# top_level.net
KiCad netlist of a schematic drawn in Altium Designer
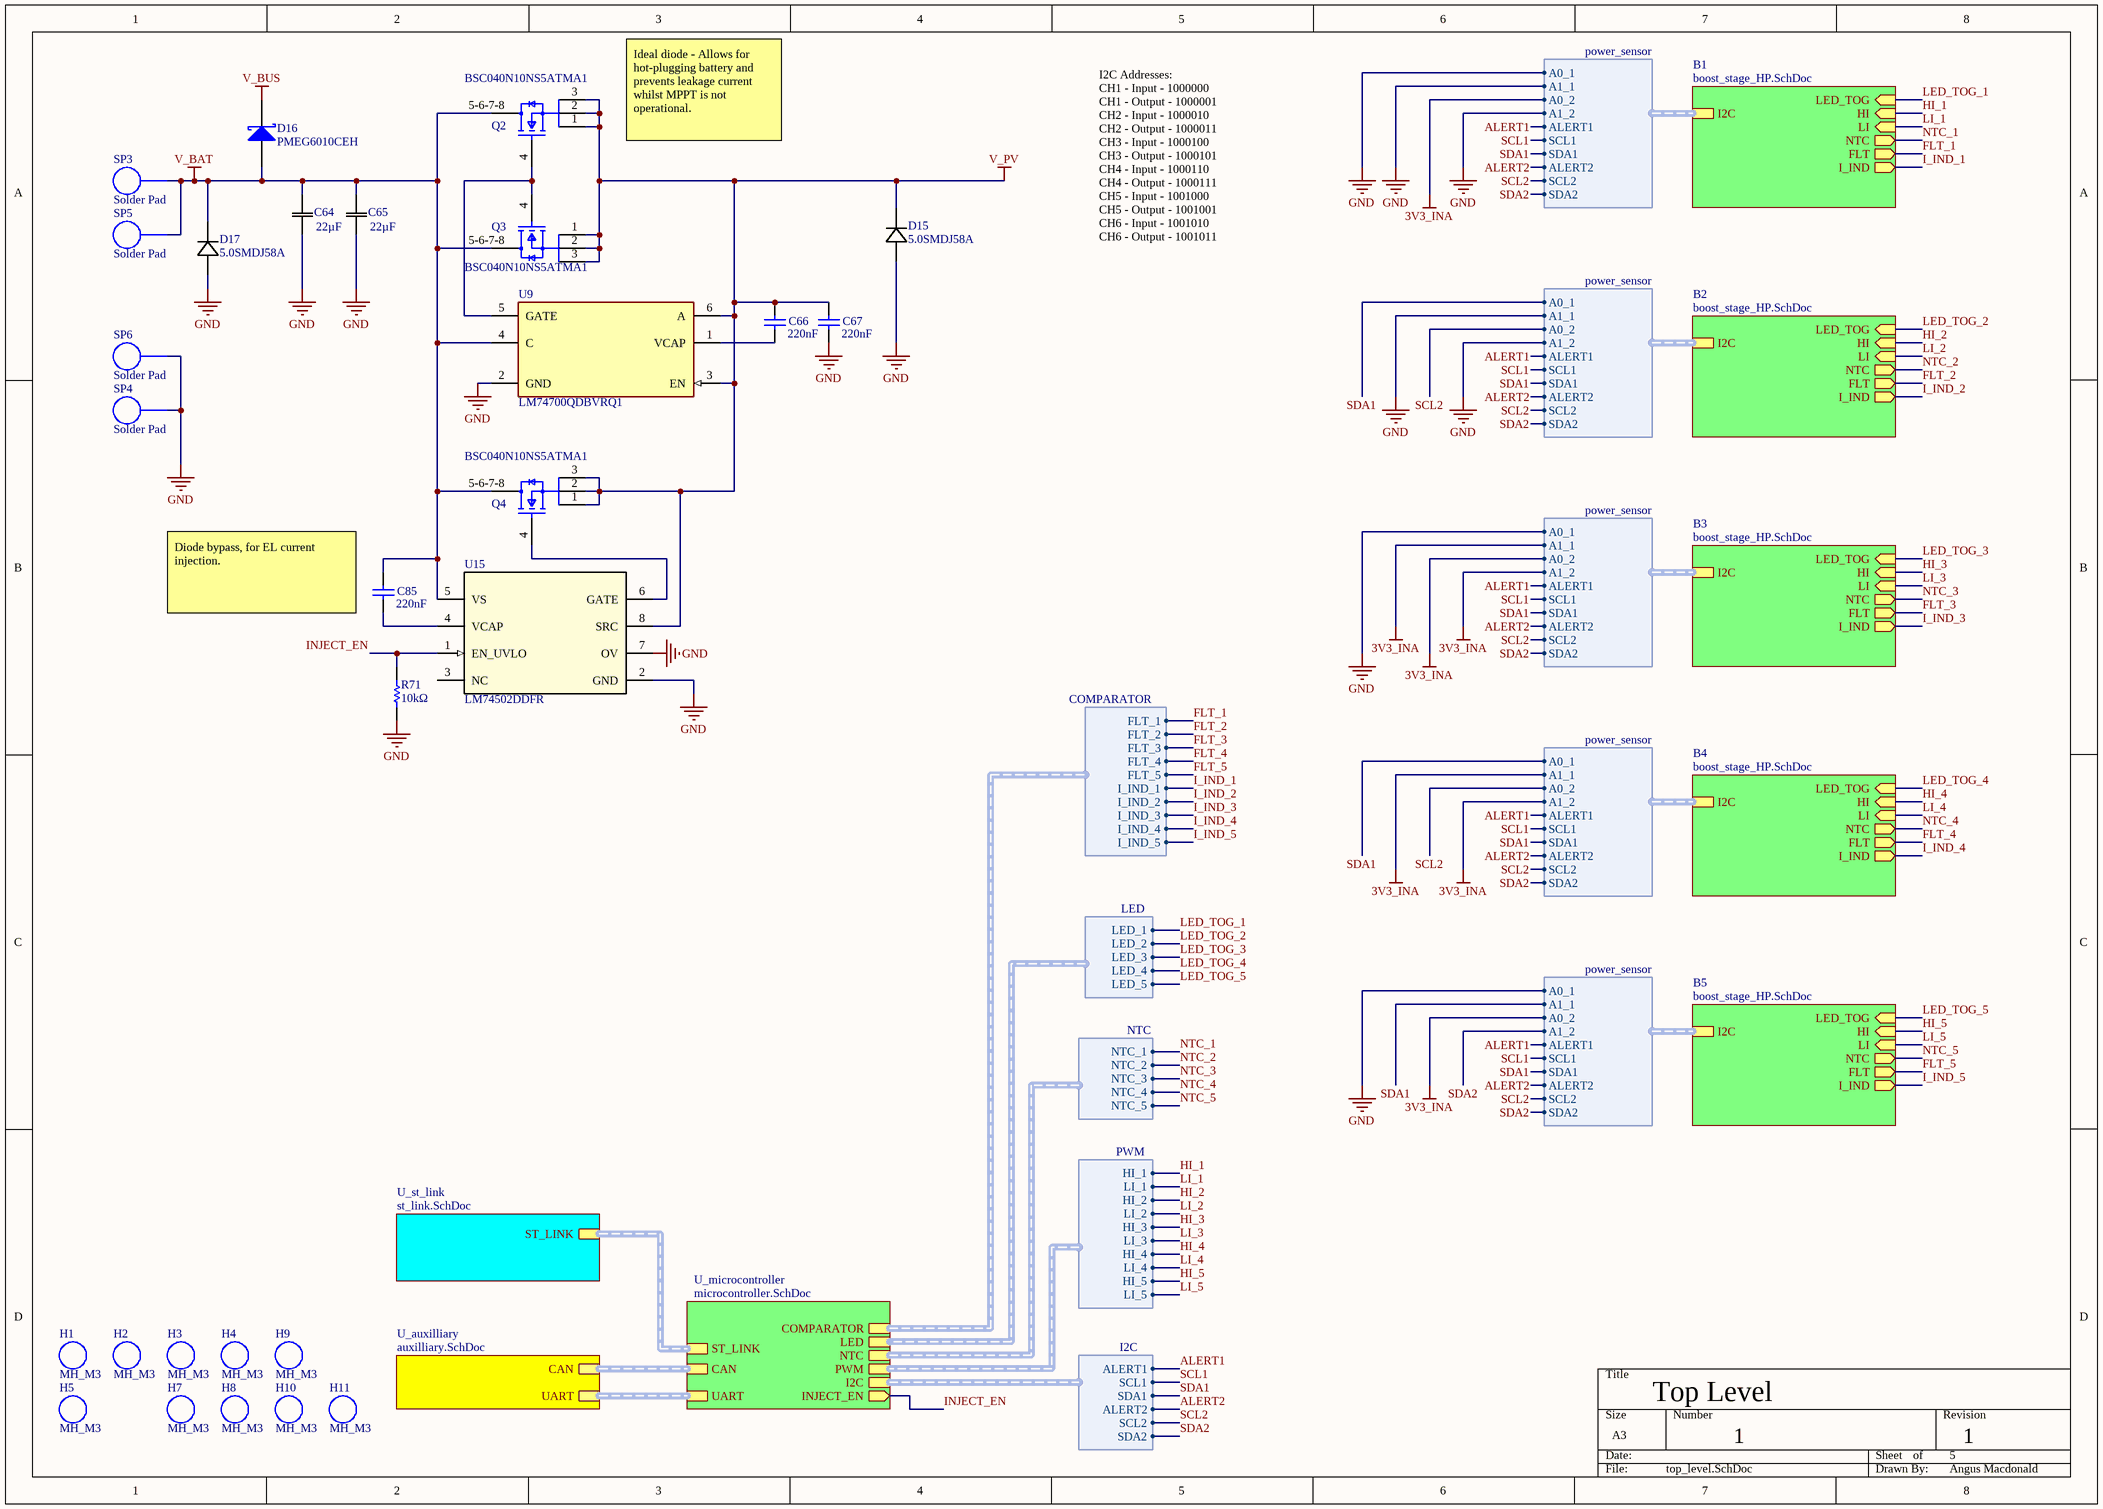
[diagram p0: top_level.SchDoc]

(export (version "E")
  (design (tool "Eeschema 10.0.6"))
  (components
    (comp (ref "C64")
      (value "22µF")
      (footprint "CAP_EEE-FK2A220P_PAN")
      (description "Radial Can - SMD ALUMINUM ELECTROLYTIC CAPACITOR FK 100V 22muF ±20% 0.315Dia 8.00mm")
      (fields
        (field (name "TOLERANCE") "20%")
        (field (name "MANUFACTURER_PART_NUMBER") "EEE-FK2A220P")
        (field (name "COPYRIGHT") "Copyright (C) 2025 Ultra Librarian. All rights reserved.")
      )
      (libsource (lib "Sunswift Racing") (part "EEE-FK2A220P"))
    )
    (comp (ref "C65")
      (value "22µF")
      (footprint "CAP_EEE-FK2A220P_PAN")
      (description "Radial Can - SMD ALUMINUM ELECTROLYTIC CAPACITOR FK 100V 22muF ±20% 0.315Dia 8.00mm")
      (fields
        (field (name "TOLERANCE") "20%")
        (field (name "MANUFACTURER_PART_NUMBER") "EEE-FK2A220P")
        (field (name "COPYRIGHT") "Copyright (C) 2025 Ultra Librarian. All rights reserved.")
      )
      (libsource (lib "Sunswift Racing") (part "EEE-FK2A220P"))
    )
    (comp (ref "C66")
      (value "220nF")
      (footprint "C0805")
      (description "Multilayer Ceramic Capacitors MLCC - SMD/SMT 100V 0.22uF X7R 0805 10%")
      (fields
        (field (name "TOLERANCE") "10%")
        (field (name "MANUFACTURER PART NUMBER") "C2012X5R1A336M125AC")
      )
      (libsource (lib "Sunswift Racing") (part "Capacitor"))
    )
    (comp (ref "C67")
      (value "220nF")
      (footprint "C0805")
      (description "Multilayer Ceramic Capacitors MLCC - SMD/SMT 100V 0.22uF X7R 0805 10%")
      (fields
        (field (name "TOLERANCE") "10%")
        (field (name "MANUFACTURER PART NUMBER") "C2012X5R1A336M125AC")
      )
      (libsource (lib "Sunswift Racing") (part "Capacitor"))
    )
    (comp (ref "C85")
      (value "220nF")
      (footprint "C0805")
      (description "Multilayer Ceramic Capacitors MLCC - SMD/SMT 100V 0.22uF X7R 0805 10%")
      (fields
        (field (name "TOLERANCE") "10%")
        (field (name "MANUFACTURER PART NUMBER") "C2012X5R1A336M125AC")
      )
      (libsource (lib "Sunswift Racing") (part "Capacitor"))
    )
    (comp (ref "D15")
      (value "5.0SMDJ58A")
      (footprint "5.0SMDJSeries_LTF")
      (description "Description")
      (fields (field (name "COPYRIGHT") "Copyright (C) 2025 Ultra Librarian. All rights reserved."))
      (libsource (lib "Sunswift Racing") (part "5.0SMDJ58A"))
    )
    (comp (ref "D16")
      (value "PMEG6010CEH")
      (footprint "FP-SOD123-IPC_A")
      (description "Rectifier Diode Schottky 1A Automotive 2-Pin SOD-123F / DIODE SCHOTTKY 60V 1A SOD123F")
      (libsource (lib "Sunswift Racing") (part "DIODE_Shottky"))
    )
    (comp (ref "D17")
      (value "5.0SMDJ58A")
      (footprint "5.0SMDJSeries_LTF")
      (description "Description")
      (fields (field (name "COPYRIGHT") "Copyright (C) 2025 Ultra Librarian. All rights reserved."))
      (libsource (lib "Sunswift Racing") (part "5.0SMDJ58A"))
    )
    (comp (ref "H1")
      (value "MH_M3")
      (footprint "MH_M3-Footprint-1")
      (description "Non-plated M3 Mounting hole.")
      (libsource (lib "Sunswift Racing") (part "M3_MH"))
    )
    (comp (ref "H2")
      (value "MH_M3")
      (footprint "MH_M3-Footprint-1")
      (description "Non-plated M3 Mounting hole.")
      (libsource (lib "Sunswift Racing") (part "M3_MH"))
    )
    (comp (ref "H3")
      (value "MH_M3")
      (footprint "MH_M3-Footprint-1")
      (description "Non-plated M3 Mounting hole.")
      (libsource (lib "Sunswift Racing") (part "M3_MH"))
    )
    (comp (ref "H4")
      (value "MH_M3")
      (footprint "MH_M3-Footprint-1")
      (description "Non-plated M3 Mounting hole.")
      (libsource (lib "Sunswift Racing") (part "M3_MH"))
    )
    (comp (ref "H5")
      (value "MH_M3")
      (footprint "MH_M3-Footprint-1")
      (description "Non-plated M3 Mounting hole.")
      (libsource (lib "Sunswift Racing") (part "M3_MH"))
    )
    (comp (ref "H7")
      (value "MH_M3")
      (footprint "MH_M3-Footprint-1")
      (description "Non-plated M3 Mounting hole.")
      (libsource (lib "Sunswift Racing") (part "M3_MH"))
    )
    (comp (ref "H8")
      (value "MH_M3")
      (footprint "MH_M3-Footprint-1")
      (description "Non-plated M3 Mounting hole.")
      (libsource (lib "Sunswift Racing") (part "M3_MH"))
    )
    (comp (ref "H9")
      (value "MH_M3")
      (footprint "MH_M3-Footprint-1")
      (description "Non-plated M3 Mounting hole.")
      (libsource (lib "Sunswift Racing") (part "M3_MH"))
    )
    (comp (ref "H10")
      (value "MH_M3")
      (footprint "MH_M3-Footprint-1")
      (description "Non-plated M3 Mounting hole.")
      (libsource (lib "Sunswift Racing") (part "M3_MH"))
    )
    (comp (ref "H11")
      (value "MH_M3")
      (footprint "MH_M3-Footprint-1")
      (description "Non-plated M3 Mounting hole.")
      (libsource (lib "Sunswift Racing") (part "M3_MH"))
    )
    (comp (ref "Q2")
      (value "BSC040N10NS5ATMA1")
      (footprint "FP-PG-TDSON-8-MFG")
      (description "On a Reel of 5000, N-Channel MOSFET, 100 A, 100 V, 8-Pin TDSON Infineon BSC040N10NS5ATMA1")
      (libsource (lib "Sunswift Racing") (part "b58911ddbc8d6ca99b46cbd56421ac7"))
    )
    (comp (ref "Q3")
      (value "BSC040N10NS5ATMA1")
      (footprint "FP-PG-TDSON-8-MFG")
      (description "On a Reel of 5000, N-Channel MOSFET, 100 A, 100 V, 8-Pin TDSON Infineon BSC040N10NS5ATMA1")
      (libsource (lib "Sunswift Racing") (part "b58911ddbc8d6ca99b46cbd56421ac7"))
    )
    (comp (ref "Q4")
      (value "BSC040N10NS5ATMA1")
      (footprint "FP-PG-TDSON-8-MFG")
      (description "On a Reel of 5000, N-Channel MOSFET, 100 A, 100 V, 8-Pin TDSON Infineon BSC040N10NS5ATMA1")
      (libsource (lib "Sunswift Racing") (part "b58911ddbc8d6ca99b46cbd56421ac7"))
    )
    (comp (ref "R71")
      (value "10kΩ")
      (footprint "RESC1608X55X25ML10T15")
      (description "10 kOhms ±1% 0.1W, 1/10W Chip Resistor 0603 (1608 Metric) Moisture Resistant Thick Film")
      (fields (field (name "TOLERANCE") "1%") (field (name "Comment") "RC0603FR-0710KL"))
      (libsource (lib "Sunswift Racing") (part "RES-2"))
    )
    (comp (ref "SP3")
      (value "Solder Pad")
      (footprint "Solder Pad-Footprint-1")
      (description "64mm^2 solder pad for wire to board connections,")
      (libsource (lib "Sunswift Racing") (part "Solder Pad-Symbol-1"))
    )
    (comp (ref "SP4")
      (value "Solder Pad")
      (footprint "Solder Pad-Footprint-1")
      (description "64mm^2 solder pad for wire to board connections,")
      (libsource (lib "Sunswift Racing") (part "Solder Pad-Symbol-1"))
    )
    (comp (ref "SP5")
      (value "Solder Pad")
      (footprint "Solder Pad-Footprint-1")
      (description "64mm^2 solder pad for wire to board connections,")
      (libsource (lib "Sunswift Racing") (part "Solder Pad-Symbol-1"))
    )
    (comp (ref "SP6")
      (value "Solder Pad")
      (footprint "Solder Pad-Footprint-1")
      (description "64mm^2 solder pad for wire to board connections,")
      (libsource (lib "Sunswift Racing") (part "Solder Pad-Symbol-1"))
    )
    (comp (ref "U9")
      (value "LM74700QDBVRQ1")
      (footprint "FP-DBV0006A-IPC_B")
      (description "3.2-V to 65-V, 80-uA IQ automotive ideal diode controller 6-SOT-23 -40 to 125")
      (libsource (lib "Sunswift Racing") (part "6c1cf2fb71eda42a9abfc060c5aeec2"))
    )
    (comp (ref "U15")
      (value "LM74502DDFR")
      (footprint "DDF0008A-IPC_A")
      (description "3.2-V to 65-V industrial RPP controller with load disconnect and OVP 8-SOT-23-THIN -40 to 125")
      (fields (field (name "COPYRIGHT") "Copyright (C) 2026 Ultra Librarian. All rights reserved."))
      (libsource (lib "Sunswift Racing") (part "LM74502DDFR"))
    )
  )
  (nets
    (net (code "20") (name "/INJECT_EN") (class "Default")
      (node (ref "R71") (pin "2") (pinfunction "2_2") (pintype "passive"))
      (node (ref "U15") (pin "1") (pinfunction "EN_UVLO_1") (pintype "input"))
    )
    (net (code "54") (name "GND") (class "Default")
      (node (ref "C64") (pin "1") (pinfunction "1_1") (pintype "passive"))
      (node (ref "C65") (pin "1") (pinfunction "1_1") (pintype "passive"))
      (node (ref "C67") (pin "1") (pinfunction "1_1") (pintype "passive"))
      (node (ref "D15") (pin "2") (pinfunction "2_2") (pintype "passive"))
      (node (ref "D17") (pin "2") (pinfunction "2_2") (pintype "passive"))
      (node (ref "R71") (pin "1") (pinfunction "1_1") (pintype "passive"))
      (node (ref "SP4") (pin "SP") (pinfunction "Solder_Pad_SP") (pintype "power_in"))
      (node (ref "SP6") (pin "SP") (pinfunction "Solder_Pad_SP") (pintype "power_in"))
      (node (ref "U15") (pin "2") (pinfunction "GND_2") (pintype "power_in"))
      (node (ref "U15") (pin "7") (pinfunction "OV_7") (pintype "passive"))
      (node (ref "U9") (pin "2") (pinfunction "GND_2") (pintype "power_in"))
    )
    (net (code "55") (name "Net-(Q2-G)") (class "Default")
      (node (ref "Q2") (pin "4") (pinfunction "G_4") (pintype "passive"))
      (node (ref "Q3") (pin "4") (pinfunction "G_4") (pintype "passive"))
      (node (ref "U9") (pin "5") (pinfunction "GATE_5") (pintype "passive"))
    )
    (net (code "56") (name "Net-(Q4-G)") (class "Default")
      (node (ref "Q4") (pin "4") (pinfunction "G_4") (pintype "passive"))
      (node (ref "U15") (pin "6") (pinfunction "GATE_6") (pintype "passive"))
    )
    (net (code "57") (name "Net-(U9-VCAP)") (class "Default")
      (node (ref "C66") (pin "1") (pinfunction "1_1") (pintype "passive"))
      (node (ref "U9") (pin "1") (pinfunction "VCAP_1") (pintype "power_in"))
    )
    (net (code "58") (name "Net-(U15-VCAP)") (class "Default")
      (node (ref "C85") (pin "1") (pinfunction "1_1") (pintype "passive"))
      (node (ref "U15") (pin "4") (pinfunction "VCAP_4") (pintype "passive"))
    )
    (net (code "59") (name "V_BAT") (class "Default")
      (node (ref "C64") (pin "2") (pinfunction "2_2") (pintype "passive"))
      (node (ref "C65") (pin "2") (pinfunction "2_2") (pintype "passive"))
      (node (ref "C85") (pin "2") (pinfunction "2_2") (pintype "passive"))
      (node (ref "D16") (pin "2") (pinfunction "A_2") (pintype "passive"))
      (node (ref "D17") (pin "1") (pinfunction "1_1") (pintype "passive"))
      (node (ref "Q2") (pin "5-6-7-8") (pinfunction "D_5-6-7-8") (pintype "passive"))
      (node (ref "Q3") (pin "5-6-7-8") (pinfunction "D_5-6-7-8") (pintype "passive"))
      (node (ref "Q4") (pin "5-6-7-8") (pinfunction "D_5-6-7-8") (pintype "passive"))
      (node (ref "SP3") (pin "SP") (pinfunction "Solder_Pad_SP") (pintype "power_in"))
      (node (ref "SP5") (pin "SP") (pinfunction "Solder_Pad_SP") (pintype "power_in"))
      (node (ref "U15") (pin "5") (pinfunction "VS_5") (pintype "power_in"))
      (node (ref "U9") (pin "4") (pinfunction "C_4") (pintype "passive"))
    )
    (net (code "60") (name "V_BUS") (class "Default")
      (node (ref "D16") (pin "1") (pinfunction "K_1") (pintype "passive"))
    )
    (net (code "61") (name "V_PV") (class "Default")
      (node (ref "C66") (pin "2") (pinfunction "2_2") (pintype "passive"))
      (node (ref "C67") (pin "2") (pinfunction "2_2") (pintype "passive"))
      (node (ref "D15") (pin "1") (pinfunction "1_1") (pintype "passive"))
      (node (ref "Q2") (pin "1") (pinfunction "S_1") (pintype "passive"))
      (node (ref "Q2") (pin "2") (pinfunction "S_2") (pintype "passive"))
      (node (ref "Q2") (pin "3") (pinfunction "S_3") (pintype "passive"))
      (node (ref "Q3") (pin "1") (pinfunction "S_1") (pintype "passive"))
      (node (ref "Q3") (pin "2") (pinfunction "S_2") (pintype "passive"))
      (node (ref "Q3") (pin "3") (pinfunction "S_3") (pintype "passive"))
      (node (ref "Q4") (pin "1") (pinfunction "S_1") (pintype "passive"))
      (node (ref "Q4") (pin "2") (pinfunction "S_2") (pintype "passive"))
      (node (ref "Q4") (pin "3") (pinfunction "S_3") (pintype "passive"))
      (node (ref "U15") (pin "8") (pinfunction "SRC_8") (pintype "passive"))
      (node (ref "U9") (pin "3") (pinfunction "EN_3") (pintype "input"))
      (node (ref "U9") (pin "6") (pinfunction "A_6") (pintype "passive"))
    )
    (net (code "62") (name "unconnected-(U15-NC-Pad3)") (class "Default")
      (node (ref "U15") (pin "3") (pinfunction "NC_3") (pintype "passive"))
    )
  )
)
